# Enclosure_100x68_PBC-AZ.net
KiCad netlist of a schematic drawn in EAGLE
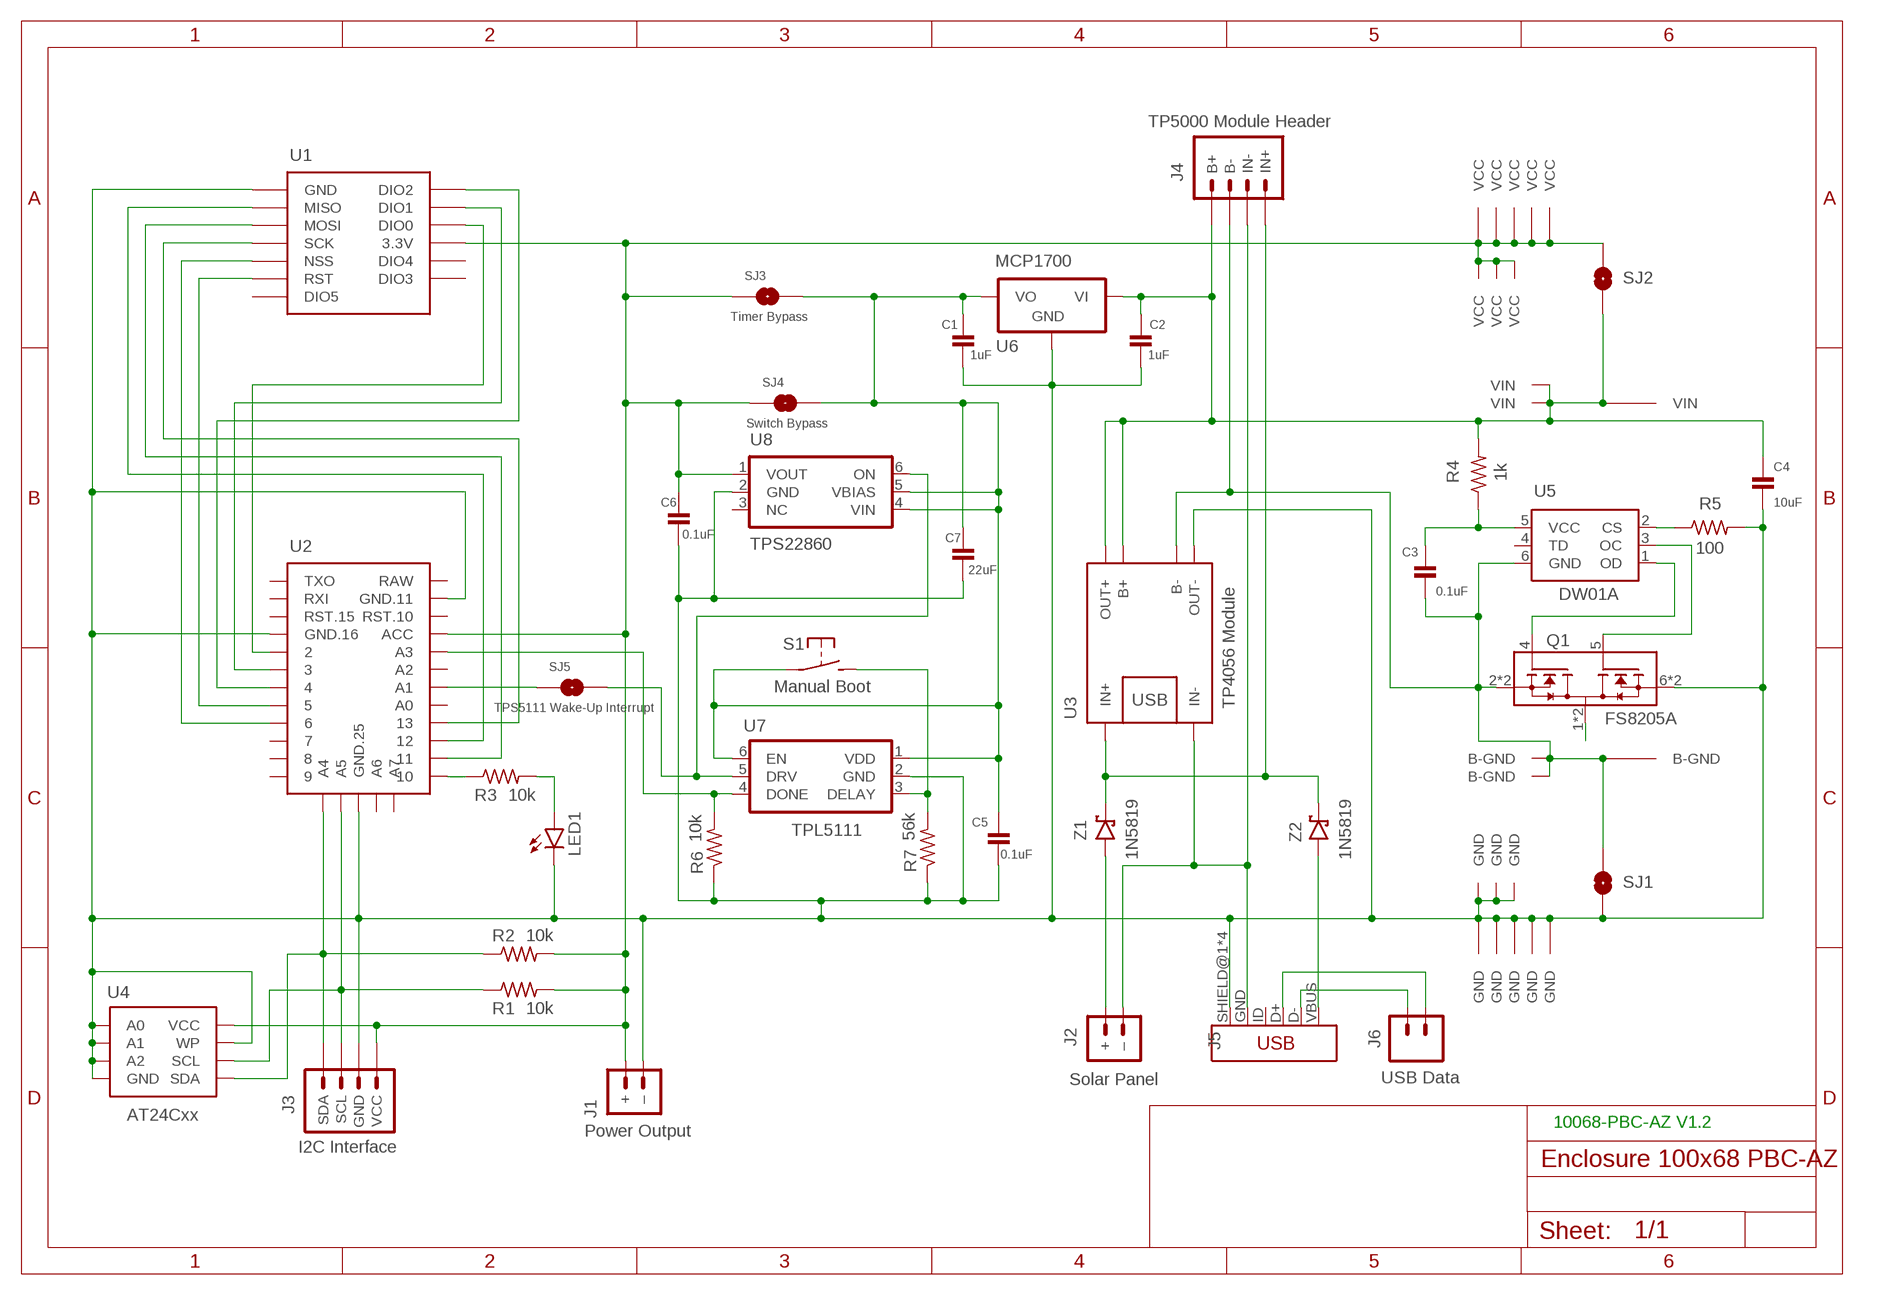
[diagram p0: schematic, sheet 1]

(export (version "E")
  (design (tool "Eeschema 10.0.6"))
  (components
    (comp (ref "C1")
      (value "1uF")
      (footprint "eagle-import:C0805")
      (libsource (lib "eagle-import") (part "CAPACITOR"))
    )
    (comp (ref "C2")
      (value "1uF")
      (footprint "eagle-import:C0805")
      (libsource (lib "eagle-import") (part "CAPACITOR"))
    )
    (comp (ref "C3")
      (value "0.1uF")
      (footprint "eagle-import:C0805")
      (libsource (lib "eagle-import") (part "CAPACITOR"))
    )
    (comp (ref "C4")
      (value "10uF")
      (footprint "eagle-import:C0805")
      (libsource (lib "eagle-import") (part "CAPACITOR"))
    )
    (comp (ref "C5")
      (value "0.1uF")
      (footprint "eagle-import:C0805")
      (libsource (lib "eagle-import") (part "CAPACITOR"))
    )
    (comp (ref "C6")
      (value "0.1uF")
      (footprint "eagle-import:C0805")
      (libsource (lib "eagle-import") (part "CAPACITOR"))
    )
    (comp (ref "C7")
      (value "22uF")
      (footprint "eagle-import:C0805")
      (libsource (lib "eagle-import") (part "CAPACITOR"))
    )
    (comp (ref "J1")
      (value "Power Output")
      (footprint "eagle-import:JST-PH1.25")
      (libsource (lib "eagle-import") (part "JST-PH1.25-MALE"))
    )
    (comp (ref "J2")
      (value "Solar Panel")
      (footprint "eagle-import:JST-PH2.0")
      (libsource (lib "eagle-import") (part "JST-PH2.0-MALE"))
    )
    (comp (ref "J3")
      (value "I2C Interface")
      (footprint "eagle-import:CONN_04-GENERIC")
      (libsource (lib "eagle-import") (part "I2C-PIN-HEADER"))
    )
    (comp (ref "J4")
      (value "TP5000 Module Header")
      (footprint "eagle-import:CONN_04-GENERIC")
      (libsource (lib "eagle-import") (part "TP5000-MODULE"))
    )
    (comp (ref "J5")
      (value "USB")
      (footprint "eagle-import:USB-MINIB")
      (libsource (lib "eagle-import") (part "USB_MINI-B_SMT"))
    )
    (comp (ref "J6")
      (value "USB Data")
      (footprint "eagle-import:CONN_02-GENERIC")
      (libsource (lib "eagle-import") (part "1X2-PIN-HEADER"))
    )
    (comp (ref "LED1")
      (value "LEDCHIP-LED0805")
      (footprint "eagle-import:CHIP-LED0805")
      (libsource (lib "eagle-import") (part "LEDCHIP-LED0805"))
    )
    (comp (ref "Q1")
      (value "FS8205A")
      (footprint "eagle-import:SOP65P640X120-8N")
      (fields (field (name "MF") "Fortune Semiconductor"))
      (libsource (lib "eagle-import") (part "FS8205A"))
    )
    (comp (ref "R1")
      (value "10k")
      (footprint "eagle-import:R0805")
      (libsource (lib "eagle-import") (part "RESISTORR0805"))
    )
    (comp (ref "R2")
      (value "10k")
      (footprint "eagle-import:R0805")
      (libsource (lib "eagle-import") (part "RESISTORR0805"))
    )
    (comp (ref "R3")
      (value "10k")
      (footprint "eagle-import:R0805")
      (libsource (lib "eagle-import") (part "RESISTORR0805"))
    )
    (comp (ref "R4")
      (value "1k")
      (footprint "eagle-import:R0805")
      (libsource (lib "eagle-import") (part "RESISTORR0805"))
    )
    (comp (ref "R5")
      (value "100")
      (footprint "eagle-import:R0805")
      (libsource (lib "eagle-import") (part "RESISTORR0805"))
    )
    (comp (ref "R6")
      (value "10k")
      (footprint "eagle-import:R0805")
      (libsource (lib "eagle-import") (part "RESISTORR0805"))
    )
    (comp (ref "R7")
      (value "56k")
      (footprint "eagle-import:R0805")
      (libsource (lib "eagle-import") (part "RESISTORR0805"))
    )
    (comp (ref "S1")
      (value "Manual Boot")
      (footprint "eagle-import:2-PAD-SWITCH")
      (libsource (lib "eagle-import") (part "2-PIN-MOMENTARY-SWITCH"))
    )
    (comp (ref "SJ3")
      (value "Timer Bypass")
      (footprint "eagle-import:SJ")
      (libsource (lib "eagle-import") (part "SJ"))
    )
    (comp (ref "SJ4")
      (value "Switch Bypass")
      (footprint "eagle-import:SJ")
      (libsource (lib "eagle-import") (part "SJ"))
    )
    (comp (ref "SJ5")
      (value "TPS5111 Wake-Up Interrupt")
      (footprint "eagle-import:SJ")
      (libsource (lib "eagle-import") (part "SJ"))
    )
    (comp (ref "U$5")
      (value "PROTO-34X22-BAT-SJ-CHG-Z")
      (footprint "eagle-import:PROTO-34X22-BAT-SJ-CHG-Z")
      (libsource (lib "eagle-import") (part "PROTO-34X22-BAT-SJ-CHG-Z"))
    )
    (comp (ref "U1")
      (value "RFM95W")
      (footprint "eagle-import:RFM95W-PI")
      (libsource (lib "eagle-import") (part "RFM95W-PI"))
    )
    (comp (ref "U2")
      (value "Arduino Pro Mini")
      (footprint "eagle-import:PRO-MINI-29")
      (libsource (lib "eagle-import") (part "ARDUINO-PRO-MINI"))
    )
    (comp (ref "U3")
      (value "TP4056 Module")
      (footprint "eagle-import:BATTERY-CHARGER-LI-PROT")
      (libsource (lib "eagle-import") (part "BATTERY-CHARGER-LI-PROT"))
    )
    (comp (ref "U4")
      (value "AT24Cxx")
      (footprint "eagle-import:SOP-8")
      (libsource (lib "eagle-import") (part "AT24CXX-EEPROM"))
    )
    (comp (ref "U5")
      (value "DW01A")
      (footprint "eagle-import:SOT23-6")
      (fields (field (name "MF") "Fortune Semiconductor"))
      (libsource (lib "eagle-import") (part "DW01A"))
    )
    (comp (ref "U6")
      (value "MCP1700")
      (footprint "eagle-import:SOT23")
      (libsource (lib "eagle-import") (part "MCP1700"))
    )
    (comp (ref "U7")
      (value "TPL5111")
      (footprint "eagle-import:SOT-23-6")
      (libsource (lib "eagle-import") (part "TPL5111DDCR"))
    )
    (comp (ref "U8")
      (value "TPS22860")
      (footprint "eagle-import:SOT-23-6")
      (libsource (lib "eagle-import") (part "TPS22860"))
    )
    (comp (ref "Z1")
      (value "1N5819")
      (footprint "eagle-import:SOD-123")
      (libsource (lib "eagle-import") (part "1N5819-SOD-123"))
    )
    (comp (ref "Z2")
      (value "1N5819")
      (footprint "eagle-import:SOD-123")
      (libsource (lib "eagle-import") (part "1N5819-SOD-123"))
    )
  )
  (nets
    (net (code "1") (name "/RAW") (class "Default")
      (node (ref "U2") (pin "RAW") (pinfunction "RAW_RAW") (pintype "power_in"))
    )
    (net (code "2") (name "Net-(J1-–)") (class "Default")
      (node (ref "C1") (pin "2") (pinfunction "2_2") (pintype "passive"))
      (node (ref "C2") (pin "2") (pinfunction "2_2") (pintype "passive"))
      (node (ref "C4") (pin "2") (pinfunction "2_2") (pintype "passive"))
      (node (ref "C5") (pin "2") (pinfunction "2_2") (pintype "passive"))
      (node (ref "C6") (pin "2") (pinfunction "2_2") (pintype "passive"))
      (node (ref "C7") (pin "2") (pinfunction "2_2") (pintype "passive"))
      (node (ref "J1") (pin "-") (pinfunction "–_-") (pintype "power_in"))
      (node (ref "J3") (pin "2") (pinfunction "GND_2") (pintype "passive"))
      (node (ref "J5") (pin "SHIELD@1") (pinfunction "SHIELD_SHIELD@1") (pintype "power_in"))
      (node (ref "J5") (pin "SHIELD@2") (pinfunction "SHIELD_SHIELD@2") (pintype "power_in"))
      (node (ref "J5") (pin "SHIELD@3") (pinfunction "SHIELD_SHIELD@3") (pintype "power_in"))
      (node (ref "J5") (pin "SHIELD@4") (pinfunction "SHIELD_SHIELD@4") (pintype "power_in"))
      (node (ref "LED1") (pin "C") (pinfunction "C_C") (pintype "passive"))
      (node (ref "Q1") (pin "6") (pinfunction "S2_6") (pintype "passive"))
      (node (ref "Q1") (pin "7") (pinfunction "S2_7") (pintype "passive"))
      (node (ref "R5") (pin "2") (pinfunction "2_2") (pintype "passive"))
      (node (ref "R6") (pin "1") (pinfunction "1_1") (pintype "passive"))
      (node (ref "R7") (pin "1") (pinfunction "1_1") (pintype "passive"))
      (node (ref "U$5") (pin "GND") (pinfunction "GND_GND") (pintype "power_in"))
      (node (ref "U$5") (pin "P33-13") (pinfunction "GND_P33-13") (pintype "power_in"))
      (node (ref "U$5") (pin "P33-14") (pinfunction "GND_P33-14") (pintype "power_in"))
      (node (ref "U$5") (pin "P33-15") (pinfunction "GND_P33-15") (pintype "power_in"))
      (node (ref "U$5") (pin "P34-13") (pinfunction "GND_P34-13") (pintype "power_in"))
      (node (ref "U$5") (pin "P34-14") (pinfunction "GND_P34-14") (pintype "power_in"))
      (node (ref "U$5") (pin "P34-15") (pinfunction "GND_P34-15") (pintype "power_in"))
      (node (ref "U$5") (pin "P34-16") (pinfunction "GND_P34-16") (pintype "power_in"))
      (node (ref "U$5") (pin "P34-17") (pinfunction "GND_P34-17") (pintype "power_in"))
      (node (ref "U1") (pin "GND@3") (pinfunction "GND_GND@3") (pintype "power_in"))
      (node (ref "U1") (pin "GND@6") (pinfunction "GND_GND@6") (pintype "power_in"))
      (node (ref "U2") (pin "GND@11") (pinfunction "GND.25_GND@11") (pintype "bidirectional"))
      (node (ref "U2") (pin "GND@16") (pinfunction "GND.16_GND@16") (pintype "power_in"))
      (node (ref "U2") (pin "GND@25") (pinfunction "GND.11_GND@25") (pintype "power_in"))
      (node (ref "U3") (pin "OUT-") (pinfunction "OUT-_OUT-") (pintype "power_in"))
      (node (ref "U4") (pin "P$1") (pinfunction "A0_P$1") (pintype "bidirectional"))
      (node (ref "U4") (pin "P$2") (pinfunction "A1_P$2") (pintype "bidirectional"))
      (node (ref "U4") (pin "P$3") (pinfunction "A2_P$3") (pintype "bidirectional"))
      (node (ref "U4") (pin "P$4") (pinfunction "GND_P$4") (pintype "bidirectional"))
      (node (ref "U4") (pin "P$7") (pinfunction "WP_P$7") (pintype "bidirectional"))
      (node (ref "U6") (pin "1") (pinfunction "GND_1") (pintype "passive"))
      (node (ref "U7") (pin "2") (pinfunction "GND_2") (pintype "power_in"))
      (node (ref "U8") (pin "2") (pinfunction "GND_2") (pintype "power_in"))
    )
    (net (code "3") (name "Net-(J2-Pad+)") (class "Default")
      (node (ref "J2") (pin "+") (pinfunction "+_+") (pintype "power_in"))
      (node (ref "Z1") (pin "A") (pinfunction "A_A") (pintype "passive"))
    )
    (net (code "4") (name "Net-(J2-–)") (class "Default")
      (node (ref "J2") (pin "-") (pinfunction "–_-") (pintype "power_in"))
      (node (ref "J4") (pin "2") (pinfunction "IN-_2") (pintype "passive"))
      (node (ref "J5") (pin "GND") (pinfunction "GND_GND") (pintype "power_in"))
      (node (ref "U3") (pin "IN-") (pinfunction "IN-_IN-") (pintype "power_in"))
    )
    (net (code "5") (name "Net-(J3-SCL)") (class "Default")
      (node (ref "J3") (pin "3") (pinfunction "SCL_3") (pintype "passive"))
      (node (ref "R1") (pin "1") (pinfunction "1_1") (pintype "passive"))
      (node (ref "U2") (pin "A5") (pinfunction "A5_A5") (pintype "bidirectional"))
      (node (ref "U4") (pin "P$6") (pinfunction "SCL_P$6") (pintype "bidirectional"))
    )
    (net (code "6") (name "Net-(J3-SDA)") (class "Default")
      (node (ref "J3") (pin "4") (pinfunction "SDA_4") (pintype "passive"))
      (node (ref "R2") (pin "1") (pinfunction "1_1") (pintype "passive"))
      (node (ref "U2") (pin "A4") (pinfunction "A4_A4") (pintype "bidirectional"))
      (node (ref "U4") (pin "P$5") (pinfunction "SDA_P$5") (pintype "bidirectional"))
    )
    (net (code "7") (name "Net-(J3-VCC)") (class "Default")
      (node (ref "C6") (pin "1") (pinfunction "1_1") (pintype "passive"))
      (node (ref "J1") (pin "+") (pinfunction "+_+") (pintype "power_in"))
      (node (ref "J3") (pin "1") (pinfunction "VCC_1") (pintype "passive"))
      (node (ref "R1") (pin "2") (pinfunction "2_2") (pintype "passive"))
      (node (ref "R2") (pin "2") (pinfunction "2_2") (pintype "passive"))
      (node (ref "SJ3") (pin "1") (pinfunction "1_1") (pintype "passive"))
      (node (ref "SJ4") (pin "1") (pinfunction "1_1") (pintype "passive"))
      (node (ref "U$5") (pin "P01-13") (pinfunction "VCC_P01-13") (pintype "power_in"))
      (node (ref "U$5") (pin "P01-14") (pinfunction "VCC_P01-14") (pintype "power_in"))
      (node (ref "U$5") (pin "P01-15") (pinfunction "VCC_P01-15") (pintype "power_in"))
      (node (ref "U$5") (pin "P01-16") (pinfunction "VCC_P01-16") (pintype "power_in"))
      (node (ref "U$5") (pin "P01-17") (pinfunction "VCC_P01-17") (pintype "power_in"))
      (node (ref "U$5") (pin "P02-13") (pinfunction "VCC_P02-13") (pintype "power_in"))
      (node (ref "U$5") (pin "P02-14") (pinfunction "VCC_P02-14") (pintype "power_in"))
      (node (ref "U$5") (pin "P02-15") (pinfunction "VCC_P02-15") (pintype "power_in"))
      (node (ref "U$5") (pin "VCC") (pinfunction "VCC_VCC") (pintype "power_in"))
      (node (ref "U1") (pin "3V3") (pinfunction "3.3V_3V3") (pintype "power_in"))
      (node (ref "U2") (pin "ACC") (pinfunction "ACC_ACC") (pintype "power_in"))
      (node (ref "U4") (pin "P$8") (pinfunction "VCC_P$8") (pintype "bidirectional"))
      (node (ref "U8") (pin "1") (pinfunction "VOUT_1") (pintype "power_in"))
    )
    (net (code "8") (name "Net-(J4-B+)") (class "Default")
      (node (ref "C2") (pin "1") (pinfunction "1_1") (pintype "passive"))
      (node (ref "C4") (pin "1") (pinfunction "1_1") (pintype "passive"))
      (node (ref "J4") (pin "4") (pinfunction "B+_4") (pintype "passive"))
      (node (ref "R4") (pin "2") (pinfunction "2_2") (pintype "passive"))
      (node (ref "U$5") (pin "P02-17") (pinfunction "VIN_P02-17") (pintype "power_in"))
      (node (ref "U$5") (pin "P03-16") (pinfunction "VIN_P03-16") (pintype "power_in"))
      (node (ref "U$5") (pin "P06-19") (pinfunction "VIN_P06-19") (pintype "power_in"))
      (node (ref "U$5") (pin "VIN") (pinfunction "VIN_VIN") (pintype "power_in"))
      (node (ref "U3") (pin "B+") (pinfunction "B+_B+") (pintype "power_in"))
      (node (ref "U3") (pin "OUT+") (pinfunction "OUT+_OUT+") (pintype "power_in"))
      (node (ref "U6") (pin "3") (pinfunction "VI_3") (pintype "input"))
    )
    (net (code "9") (name "Net-(J4-B-)") (class "Default")
      (node (ref "C3") (pin "2") (pinfunction "2_2") (pintype "passive"))
      (node (ref "J4") (pin "3") (pinfunction "B-_3") (pintype "passive"))
      (node (ref "Q1") (pin "2") (pinfunction "S1_2") (pintype "passive"))
      (node (ref "Q1") (pin "3") (pinfunction "S1_3") (pintype "passive"))
      (node (ref "U$5") (pin "B-GND") (pinfunction "B-GND_B-GND") (pintype "power_in"))
      (node (ref "U$5") (pin "P28-19") (pinfunction "B-GND_P28-19") (pintype "power_in"))
      (node (ref "U$5") (pin "P32-16") (pinfunction "B-GND_P32-16") (pintype "power_in"))
      (node (ref "U$5") (pin "P33-17") (pinfunction "B-GND_P33-17") (pintype "power_in"))
      (node (ref "U3") (pin "B-") (pinfunction "B-_B-") (pintype "power_in"))
      (node (ref "U5") (pin "6") (pinfunction "GND_6") (pintype "power_in"))
    )
    (net (code "10") (name "Net-(J4-IN+)") (class "Default")
      (node (ref "J4") (pin "1") (pinfunction "IN+_1") (pintype "passive"))
      (node (ref "U3") (pin "IN+") (pinfunction "IN+_IN+") (pintype "power_in"))
      (node (ref "Z1") (pin "C") (pinfunction "C_C") (pintype "passive"))
      (node (ref "Z2") (pin "C") (pinfunction "C_C") (pintype "passive"))
    )
    (net (code "11") (name "Net-(J5-PadD+)") (class "Default")
      (node (ref "J5") (pin "D+") (pinfunction "D+_D+") (pintype "bidirectional"))
      (node (ref "J6") (pin "2") (pinfunction "2_2") (pintype "passive"))
    )
    (net (code "12") (name "Net-(J5-PadD-)") (class "Default")
      (node (ref "J5") (pin "D-") (pinfunction "D-_D-") (pintype "bidirectional"))
      (node (ref "J6") (pin "1") (pinfunction "1_1") (pintype "passive"))
    )
    (net (code "13") (name "Net-(J5-PadVBUS)") (class "Default")
      (node (ref "J5") (pin "VBUS") (pinfunction "VBUS_VBUS") (pintype "power_in"))
      (node (ref "Z2") (pin "A") (pinfunction "A_A") (pintype "passive"))
    )
    (net (code "14") (name "Net-(LED1-PadA)") (class "Default")
      (node (ref "LED1") (pin "A") (pinfunction "A_A") (pintype "passive"))
      (node (ref "R3") (pin "2") (pinfunction "2_2") (pintype "passive"))
    )
    (net (code "15") (name "Net-(Q1-D12-Pad1)") (class "Default")
      (node (ref "Q1") (pin "1") (pinfunction "D12_1") (pintype "passive"))
      (node (ref "Q1") (pin "8") (pinfunction "D12_8") (pintype "passive"))
    )
    (net (code "16") (name "Net-(Q1-G1)") (class "Default")
      (node (ref "Q1") (pin "4") (pinfunction "G1_4") (pintype "passive"))
      (node (ref "U5") (pin "1") (pinfunction "OD_1") (pintype "bidirectional"))
    )
    (net (code "17") (name "Net-(Q1-G2)") (class "Default")
      (node (ref "Q1") (pin "5") (pinfunction "G2_5") (pintype "passive"))
      (node (ref "U5") (pin "3") (pinfunction "OC_3") (pintype "bidirectional"))
    )
    (net (code "18") (name "Net-(R3-Pad1)") (class "Default")
      (node (ref "R3") (pin "1") (pinfunction "1_1") (pintype "passive"))
      (node (ref "U2") (pin "10") (pinfunction "10_10") (pintype "bidirectional"))
    )
    (net (code "19") (name "Net-(S1-P)") (class "Default")
      (node (ref "C1") (pin "1") (pinfunction "1_1") (pintype "passive"))
      (node (ref "C5") (pin "1") (pinfunction "1_1") (pintype "passive"))
      (node (ref "C7") (pin "1") (pinfunction "1_1") (pintype "passive"))
      (node (ref "S1") (pin "P$1") (pinfunction "P_P$1") (pintype "passive"))
      (node (ref "SJ3") (pin "2") (pinfunction "2_2") (pintype "passive"))
      (node (ref "SJ4") (pin "2") (pinfunction "2_2") (pintype "passive"))
      (node (ref "U6") (pin "2") (pinfunction "VO_2") (pintype "output"))
      (node (ref "U7") (pin "1") (pinfunction "VDD_1") (pintype "power_in"))
      (node (ref "U7") (pin "6") (pinfunction "EN_6") (pintype "input"))
      (node (ref "U8") (pin "4") (pinfunction "VIN_4") (pintype "power_in"))
      (node (ref "U8") (pin "5") (pinfunction "VBIAS_5") (pintype "input"))
    )
    (net (code "20") (name "Net-(S1-S)") (class "Default")
      (node (ref "R7") (pin "2") (pinfunction "2_2") (pintype "passive"))
      (node (ref "S1") (pin "P$2") (pinfunction "S_P$2") (pintype "passive"))
      (node (ref "U7") (pin "3") (pinfunction "DELAY_3") (pintype "input"))
    )
    (net (code "21") (name "Net-(SJ5-Pad1)") (class "Default")
      (node (ref "SJ5") (pin "1") (pinfunction "1_1") (pintype "passive"))
      (node (ref "U2") (pin "A1") (pinfunction "A1_A1") (pintype "bidirectional"))
    )
    (net (code "22") (name "Net-(U1-PadDIO0)") (class "Default")
      (node (ref "U1") (pin "DIO0") (pinfunction "DIO0_DIO0") (pintype "bidirectional"))
      (node (ref "U2") (pin "2") (pinfunction "2_2") (pintype "bidirectional"))
    )
    (net (code "23") (name "Net-(U1-PadDIO1)") (class "Default")
      (node (ref "U1") (pin "DIO1") (pinfunction "DIO1_DIO1") (pintype "bidirectional"))
      (node (ref "U2") (pin "3") (pinfunction "3_3") (pintype "bidirectional"))
    )
    (net (code "24") (name "Net-(U1-PadDIO2)") (class "Default")
      (node (ref "U1") (pin "DIO2") (pinfunction "DIO2_DIO2") (pintype "bidirectional"))
      (node (ref "U2") (pin "4") (pinfunction "4_4") (pintype "bidirectional"))
    )
    (net (code "25") (name "Net-(U1-PadMISO)") (class "Default")
      (node (ref "U1") (pin "MISO") (pinfunction "MISO_MISO") (pintype "bidirectional"))
      (node (ref "U2") (pin "12") (pinfunction "12_12") (pintype "bidirectional"))
    )
    (net (code "26") (name "Net-(U1-PadMOSI)") (class "Default")
      (node (ref "U1") (pin "MOSI") (pinfunction "MOSI_MOSI") (pintype "bidirectional"))
      (node (ref "U2") (pin "11") (pinfunction "11_11") (pintype "bidirectional"))
    )
    (net (code "27") (name "Net-(U1-PadNSS)") (class "Default")
      (node (ref "U1") (pin "NSS") (pinfunction "NSS_NSS") (pintype "bidirectional"))
      (node (ref "U2") (pin "6") (pinfunction "6_6") (pintype "bidirectional"))
    )
    (net (code "28") (name "Net-(U1-PadRST)") (class "Default")
      (node (ref "U1") (pin "RST") (pinfunction "RST_RST") (pintype "bidirectional"))
      (node (ref "U2") (pin "5") (pinfunction "5_5") (pintype "bidirectional"))
    )
    (net (code "29") (name "Net-(U1-PadSCK)") (class "Default")
      (node (ref "U1") (pin "SCK") (pinfunction "SCK_SCK") (pintype "bidirectional"))
      (node (ref "U2") (pin "13") (pinfunction "13_13") (pintype "bidirectional"))
    )
    (net (code "30") (name "Net-(U5-CS)") (class "Default")
      (node (ref "R5") (pin "1") (pinfunction "1_1") (pintype "passive"))
      (node (ref "U5") (pin "2") (pinfunction "CS_2") (pintype "bidirectional"))
    )
    (net (code "31") (name "Net-(U5-VCC)") (class "Default")
      (node (ref "C3") (pin "1") (pinfunction "1_1") (pintype "passive"))
      (node (ref "R4") (pin "1") (pinfunction "1_1") (pintype "passive"))
      (node (ref "U5") (pin "5") (pinfunction "VCC_5") (pintype "power_in"))
    )
    (net (code "32") (name "Net-(U7-DONE)") (class "Default")
      (node (ref "R6") (pin "2") (pinfunction "2_2") (pintype "passive"))
      (node (ref "U2") (pin "A3") (pinfunction "A3_A3") (pintype "bidirectional"))
      (node (ref "U7") (pin "4") (pinfunction "DONE_4") (pintype "input"))
    )
    (net (code "33") (name "Net-(U7-DRV)") (class "Default")
      (node (ref "SJ5") (pin "2") (pinfunction "2_2") (pintype "passive"))
      (node (ref "U7") (pin "5") (pinfunction "DRV_5") (pintype "output"))
      (node (ref "U8") (pin "6") (pinfunction "ON_6") (pintype "input"))
    )
    (net (code "34") (name "unconnected-(J5-PadID)") (class "Default")
      (node (ref "J5") (pin "ID") (pinfunction "ID_ID") (pintype "bidirectional"))
    )
    (net (code "35") (name "unconnected-(U1-PadDIO3)") (class "Default")
      (node (ref "U1") (pin "DIO3") (pinfunction "DIO3_DIO3") (pintype "bidirectional"))
    )
    (net (code "36") (name "unconnected-(U1-PadDIO4)") (class "Default")
      (node (ref "U1") (pin "DIO4") (pinfunction "DIO4_DIO4") (pintype "bidirectional"))
    )
    (net (code "37") (name "unconnected-(U1-PadDIO5)") (class "Default")
      (node (ref "U1") (pin "DIO5") (pinfunction "DIO5_DIO5") (pintype "bidirectional"))
    )
    (net (code "38") (name "unconnected-(U2-Pad7)") (class "Default")
      (node (ref "U2") (pin "7") (pinfunction "7_7") (pintype "bidirectional"))
    )
    (net (code "39") (name "unconnected-(U2-Pad8)") (class "Default")
      (node (ref "U2") (pin "8") (pinfunction "8_8") (pintype "bidirectional"))
    )
    (net (code "40") (name "unconnected-(U2-Pad9)") (class "Default")
      (node (ref "U2") (pin "9") (pinfunction "9_9") (pintype "bidirectional"))
    )
    (net (code "41") (name "unconnected-(U2-PadA0)") (class "Default")
      (node (ref "U2") (pin "A0") (pinfunction "A0_A0") (pintype "bidirectional"))
    )
    (net (code "42") (name "unconnected-(U2-PadA2)") (class "Default")
      (node (ref "U2") (pin "A2") (pinfunction "A2_A2") (pintype "bidirectional"))
    )
    (net (code "43") (name "unconnected-(U2-PadA6)") (class "Default")
      (node (ref "U2") (pin "A6") (pinfunction "A6_A6") (pintype "bidirectional"))
    )
    (net (code "44") (name "unconnected-(U2-PadA7)") (class "Default")
      (node (ref "U2") (pin "A7") (pinfunction "A7_A7") (pintype "bidirectional"))
    )
    (net (code "45") (name "unconnected-(U2-PadRXI)") (class "Default")
      (node (ref "U2") (pin "RXI") (pinfunction "RXI_RXI") (pintype "input"))
    )
    (net (code "46") (name "unconnected-(U2-PadTXO)") (class "Default")
      (node (ref "U2") (pin "TXO") (pinfunction "TXO_TXO") (pintype "bidirectional"))
    )
    (net (code "47") (name "unconnected-(U2-RST.10-PadRST@10)") (class "Default")
      (node (ref "U2") (pin "RST@10") (pinfunction "RST.10_RST@10") (pintype "input"))
    )
    (net (code "48") (name "unconnected-(U2-RST.15-PadRST@15)") (class "Default")
      (node (ref "U2") (pin "RST@15") (pinfunction "RST.15_RST@15") (pintype "input"))
    )
    (net (code "49") (name "unconnected-(U5-TD-Pad4)") (class "Default")
      (node (ref "U5") (pin "4") (pinfunction "TD_4") (pintype "bidirectional"))
    )
    (net (code "50") (name "unconnected-(U8-NC-Pad3)") (class "Default")
      (node (ref "U8") (pin "3") (pinfunction "NC_3") (pintype "no_connect"))
    )
  )
)
